# User_Interface.net
KiCad netlist of a schematic drawn in Altium Designer
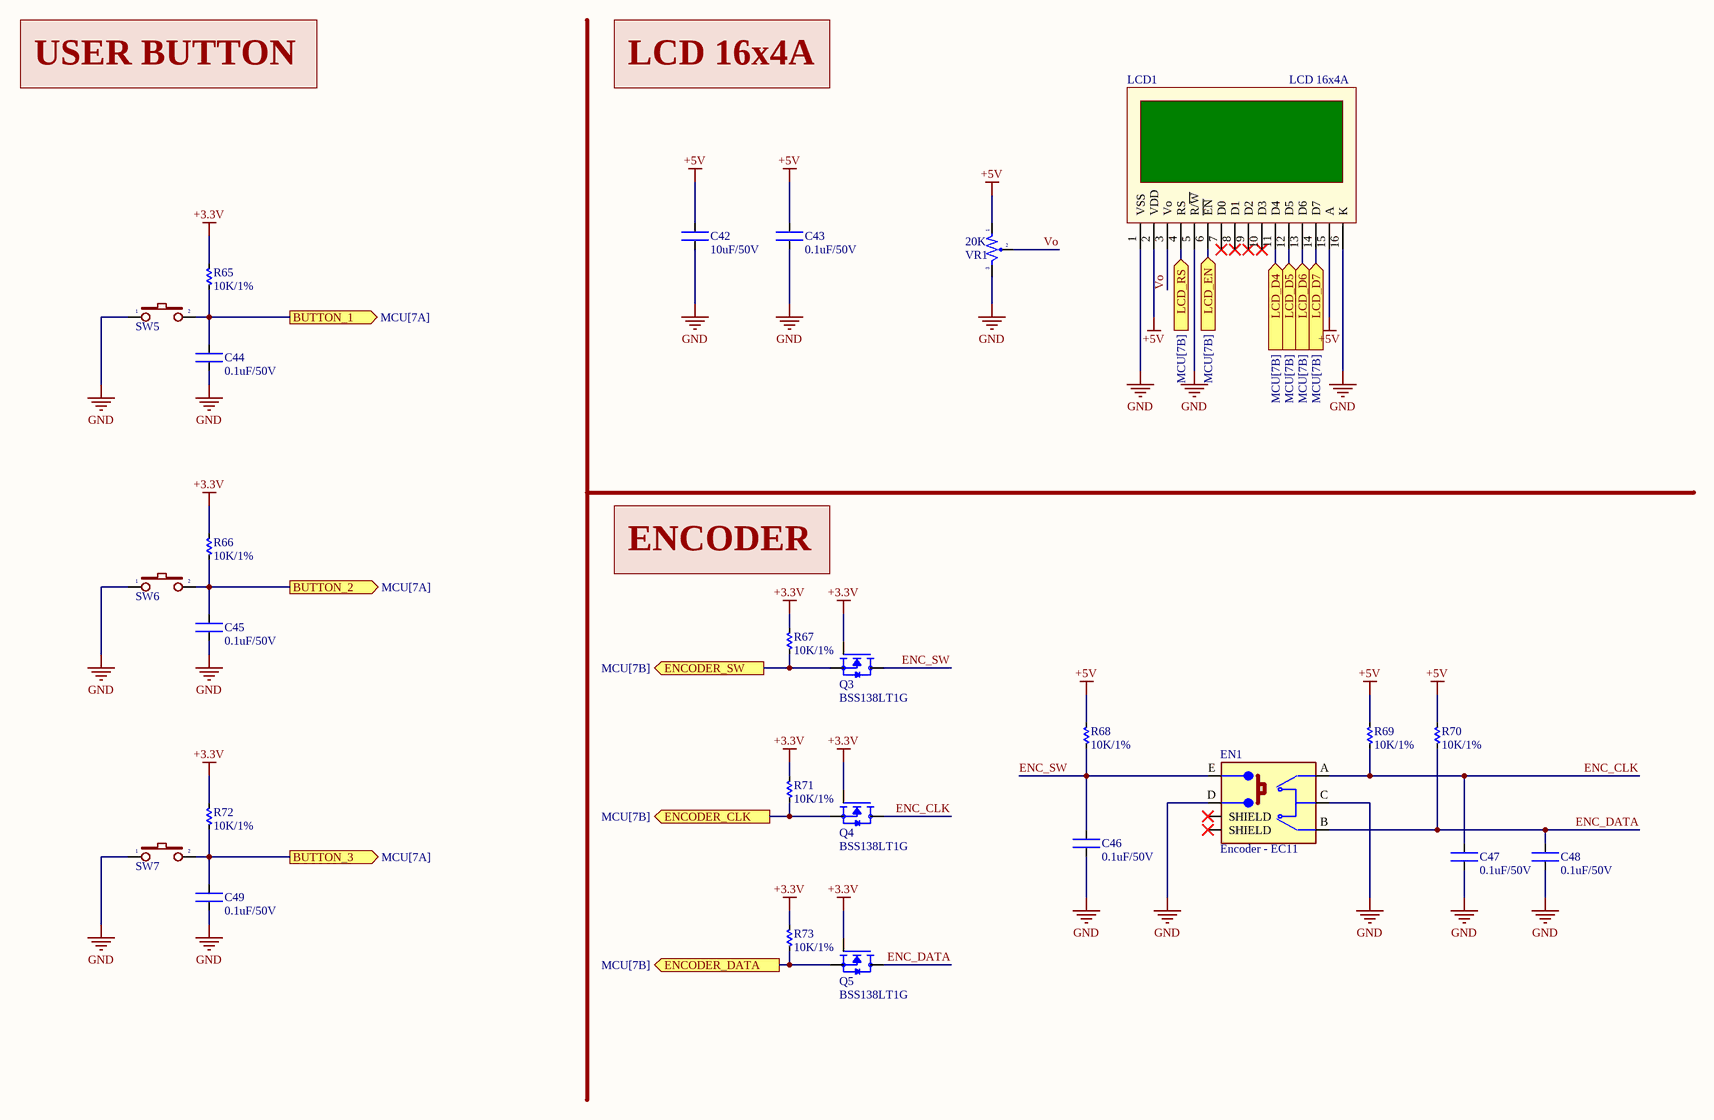
[diagram p0: User_Interface.SchDoc]

(export (version "E")
  (design (tool "Eeschema 10.0.6"))
  (components
    (comp (ref "C42")
      (value "10uF/50V")
      (footprint "CAP - 0603")
      (description "CAPACITOR SMD - KEMET")
      (libsource (lib "NewLibrary") (part "CAPACITOR"))
    )
    (comp (ref "C43")
      (value "0.1uF/50V")
      (footprint "CAP - 0603")
      (description "CAPACITOR SMD - KEMET")
      (libsource (lib "NewLibrary") (part "CAPACITOR"))
    )
    (comp (ref "C44")
      (value "0.1uF/50V")
      (footprint "CAP - 0603")
      (description "CAPACITOR SMD - KEMET")
      (libsource (lib "NewLibrary") (part "CAPACITOR"))
    )
    (comp (ref "C45")
      (value "0.1uF/50V")
      (footprint "CAP - 0603")
      (description "CAPACITOR SMD - KEMET")
      (libsource (lib "NewLibrary") (part "CAPACITOR"))
    )
    (comp (ref "C46")
      (value "0.1uF/50V")
      (footprint "CAP - 0603")
      (description "CAPACITOR SMD - KEMET")
      (libsource (lib "NewLibrary") (part "CAPACITOR"))
    )
    (comp (ref "C47")
      (value "0.1uF/50V")
      (footprint "CAP - 0603")
      (description "CAPACITOR SMD - KEMET")
      (libsource (lib "NewLibrary") (part "CAPACITOR"))
    )
    (comp (ref "C48")
      (value "0.1uF/50V")
      (footprint "CAP - 0603")
      (description "CAPACITOR SMD - KEMET")
      (libsource (lib "NewLibrary") (part "CAPACITOR"))
    )
    (comp (ref "C49")
      (value "0.1uF/50V")
      (footprint "CAP - 0603")
      (description "CAPACITOR SMD - KEMET")
      (libsource (lib "NewLibrary") (part "CAPACITOR"))
    )
    (comp (ref "EN1")
      (value "Encoder - EC11")
      (footprint "Encoder - EC11")
      (description "Bourns PEC11R-4015F-S0024")
      (libsource (lib "NewLibrary") (part "Encoder - EC11"))
    )
    (comp (ref "LCD1")
      (value "LCD 16x4A")
      (footprint "LCD-16x4A-2-Holes")
      (description "Character LCD, 16x4, LED backlight.")
      (libsource (lib "NewLibrary") (part "LCD 16x4A"))
    )
    (comp (ref "Q3")
      (value "BSS138LT1G")
      (footprint "SOT23-3 - BSS138LT1G")
      (description "N-Channel 50 V 200mA (Ta) 225mW (Ta) Surface Mount SOT-23-3 (TO-236)")
      (libsource (lib "NewLibrary") (part "BSS138LT1G"))
    )
    (comp (ref "Q4")
      (value "BSS138LT1G")
      (footprint "SOT23-3 - BSS138LT1G")
      (description "N-Channel 50 V 200mA (Ta) 225mW (Ta) Surface Mount SOT-23-3 (TO-236)")
      (libsource (lib "NewLibrary") (part "BSS138LT1G"))
    )
    (comp (ref "Q5")
      (value "BSS138LT1G")
      (footprint "SOT23-3 - BSS138LT1G")
      (description "N-Channel 50 V 200mA (Ta) 225mW (Ta) Surface Mount SOT-23-3 (TO-236)")
      (libsource (lib "NewLibrary") (part "BSS138LT1G"))
    )
    (comp (ref "R65")
      (value "10K/1%")
      (footprint "RES - 0603")
      (description "Resistor SMD - YAGEO")
      (libsource (lib "NewLibrary") (part "RESISTOR"))
    )
    (comp (ref "R66")
      (value "10K/1%")
      (footprint "RES - 0603")
      (description "Resistor SMD - YAGEO")
      (libsource (lib "NewLibrary") (part "RESISTOR"))
    )
    (comp (ref "R67")
      (value "10K/1%")
      (footprint "RES - 0603")
      (description "Resistor SMD - YAGEO")
      (libsource (lib "NewLibrary") (part "RESISTOR"))
    )
    (comp (ref "R68")
      (value "10K/1%")
      (footprint "RES - 0603")
      (description "Resistor SMD - YAGEO")
      (libsource (lib "NewLibrary") (part "RESISTOR"))
    )
    (comp (ref "R69")
      (value "10K/1%")
      (footprint "RES - 0603")
      (description "Resistor SMD - YAGEO")
      (libsource (lib "NewLibrary") (part "RESISTOR"))
    )
    (comp (ref "R70")
      (value "10K/1%")
      (footprint "RES - 0603")
      (description "Resistor SMD - YAGEO")
      (libsource (lib "NewLibrary") (part "RESISTOR"))
    )
    (comp (ref "R71")
      (value "10K/1%")
      (footprint "RES - 0603")
      (description "Resistor SMD - YAGEO")
      (libsource (lib "NewLibrary") (part "RESISTOR"))
    )
    (comp (ref "R72")
      (value "10K/1%")
      (footprint "RES - 0603")
      (description "Resistor SMD - YAGEO")
      (libsource (lib "NewLibrary") (part "RESISTOR"))
    )
    (comp (ref "R73")
      (value "10K/1%")
      (footprint "RES - 0603")
      (description "Resistor SMD - YAGEO")
      (libsource (lib "NewLibrary") (part "RESISTOR"))
    )
    (comp (ref "SW5")
      (value "Button 4 Pins")
      (footprint "SW-SMD-6x6mm")
      (description "DIP Button 4 Pins")
      (libsource (lib "NewLibrary") (part "Button 4 Pins"))
    )
    (comp (ref "SW6")
      (value "Button 4 Pins")
      (footprint "SW-SMD-6x6mm")
      (description "DIP Button 4 Pins")
      (libsource (lib "NewLibrary") (part "Button 4 Pins"))
    )
    (comp (ref "SW7")
      (value "Button 4 Pins")
      (footprint "SW-SMD-6x6mm")
      (description "DIP Button 4 Pins")
      (libsource (lib "NewLibrary") (part "Button 4 Pins"))
    )
    (comp (ref "VR1")
      (value "20K")
      (footprint "VR 3x3")
      (description "VR")
      (libsource (lib "NewLibrary") (part "VARIABLE RESISTOR"))
    )
  )
  (nets
    (net (code "1") (name "+3.3V") (class "Default")
      (node (ref "Q3") (pin "1") (pinfunction "G_1") (pintype "passive"))
      (node (ref "Q4") (pin "1") (pinfunction "G_1") (pintype "passive"))
      (node (ref "Q5") (pin "1") (pinfunction "G_1") (pintype "passive"))
      (node (ref "R65") (pin "2") (pinfunction "2_2") (pintype "passive"))
      (node (ref "R66") (pin "2") (pinfunction "2_2") (pintype "passive"))
      (node (ref "R67") (pin "2") (pinfunction "2_2") (pintype "passive"))
      (node (ref "R71") (pin "2") (pinfunction "2_2") (pintype "passive"))
      (node (ref "R72") (pin "1") (pinfunction "1_1") (pintype "passive"))
      (node (ref "R73") (pin "2") (pinfunction "2_2") (pintype "passive"))
    )
    (net (code "2") (name "+5V") (class "Default")
      (node (ref "C42") (pin "2") (pinfunction "2_2") (pintype "passive"))
      (node (ref "C43") (pin "2") (pinfunction "2_2") (pintype "passive"))
      (node (ref "LCD1") (pin "15") (pinfunction "A_15") (pintype "passive"))
      (node (ref "LCD1") (pin "2") (pinfunction "VDD_2") (pintype "passive"))
      (node (ref "R68") (pin "2") (pinfunction "2_2") (pintype "passive"))
      (node (ref "R69") (pin "2") (pinfunction "2_2") (pintype "passive"))
      (node (ref "R70") (pin "2") (pinfunction "2_2") (pintype "passive"))
      (node (ref "VR1") (pin "1") (pinfunction "1_1") (pintype "passive"))
    )
    (net (code "3") (name "/BUTTON_1") (class "Default")
      (node (ref "C44") (pin "2") (pinfunction "2_2") (pintype "passive"))
      (node (ref "R65") (pin "1") (pinfunction "1_1") (pintype "passive"))
      (node (ref "SW5") (pin "2") (pinfunction "2_2") (pintype "passive"))
    )
    (net (code "4") (name "/BUTTON_2") (class "Default")
      (node (ref "C45") (pin "2") (pinfunction "2_2") (pintype "passive"))
      (node (ref "R66") (pin "1") (pinfunction "1_1") (pintype "passive"))
      (node (ref "SW6") (pin "2") (pinfunction "2_2") (pintype "passive"))
    )
    (net (code "5") (name "/BUTTON_3") (class "Default")
      (node (ref "C49") (pin "2") (pinfunction "2_2") (pintype "passive"))
      (node (ref "R72") (pin "2") (pinfunction "2_2") (pintype "passive"))
      (node (ref "SW7") (pin "2") (pinfunction "2_2") (pintype "passive"))
    )
    (net (code "6") (name "/ENCODER_CLK") (class "Default")
      (node (ref "Q4") (pin "2") (pinfunction "S_2") (pintype "passive"))
      (node (ref "R71") (pin "1") (pinfunction "1_1") (pintype "passive"))
    )
    (net (code "7") (name "/ENCODER_DATA") (class "Default")
      (node (ref "Q5") (pin "2") (pinfunction "S_2") (pintype "passive"))
      (node (ref "R73") (pin "1") (pinfunction "1_1") (pintype "passive"))
    )
    (net (code "8") (name "/ENCODER_SW") (class "Default")
      (node (ref "Q3") (pin "2") (pinfunction "S_2") (pintype "passive"))
      (node (ref "R67") (pin "1") (pinfunction "1_1") (pintype "passive"))
    )
    (net (code "9") (name "/ENC_CLK") (class "Default")
      (node (ref "C47") (pin "2") (pinfunction "2_2") (pintype "passive"))
      (node (ref "EN1") (pin "A") (pinfunction "A_A") (pintype "passive"))
      (node (ref "Q4") (pin "3") (pinfunction "D_3") (pintype "passive"))
      (node (ref "R69") (pin "1") (pinfunction "1_1") (pintype "passive"))
    )
    (net (code "10") (name "/ENC_DATA") (class "Default")
      (node (ref "C48") (pin "2") (pinfunction "2_2") (pintype "passive"))
      (node (ref "EN1") (pin "B") (pinfunction "B_B") (pintype "passive"))
      (node (ref "Q5") (pin "3") (pinfunction "D_3") (pintype "passive"))
      (node (ref "R70") (pin "1") (pinfunction "1_1") (pintype "passive"))
    )
    (net (code "11") (name "/ENC_SW") (class "Default")
      (node (ref "C46") (pin "2") (pinfunction "2_2") (pintype "passive"))
      (node (ref "EN1") (pin "E") (pinfunction "S2_E") (pintype "passive"))
      (node (ref "Q3") (pin "3") (pinfunction "D_3") (pintype "passive"))
      (node (ref "R68") (pin "1") (pinfunction "1_1") (pintype "passive"))
    )
    (net (code "12") (name "/LCD_D4") (class "Default")
      (node (ref "LCD1") (pin "11") (pinfunction "D4_11") (pintype "passive"))
    )
    (net (code "13") (name "/LCD_D5") (class "Default")
      (node (ref "LCD1") (pin "12") (pinfunction "D5_12") (pintype "passive"))
    )
    (net (code "14") (name "/LCD_D6") (class "Default")
      (node (ref "LCD1") (pin "13") (pinfunction "D6_13") (pintype "passive"))
    )
    (net (code "15") (name "/LCD_D7") (class "Default")
      (node (ref "LCD1") (pin "14") (pinfunction "D7_14") (pintype "passive"))
    )
    (net (code "16") (name "/LCD_EN") (class "Default")
      (node (ref "LCD1") (pin "6") (pinfunction "~{EN}_6") (pintype "passive"))
    )
    (net (code "17") (name "/LCD_RS") (class "Default")
      (node (ref "LCD1") (pin "4") (pinfunction "RS_4") (pintype "passive"))
    )
    (net (code "18") (name "/Vo") (class "Default")
      (node (ref "LCD1") (pin "3") (pinfunction "Vo_3") (pintype "passive"))
      (node (ref "VR1") (pin "2") (pinfunction "2_2") (pintype "passive"))
    )
    (net (code "19") (name "GND") (class "Default")
      (node (ref "C42") (pin "1") (pinfunction "1_1") (pintype "passive"))
      (node (ref "C43") (pin "1") (pinfunction "1_1") (pintype "passive"))
      (node (ref "C44") (pin "1") (pinfunction "1_1") (pintype "passive"))
      (node (ref "C45") (pin "1") (pinfunction "1_1") (pintype "passive"))
      (node (ref "C46") (pin "1") (pinfunction "1_1") (pintype "passive"))
      (node (ref "C47") (pin "1") (pinfunction "1_1") (pintype "passive"))
      (node (ref "C48") (pin "1") (pinfunction "1_1") (pintype "passive"))
      (node (ref "C49") (pin "1") (pinfunction "1_1") (pintype "passive"))
      (node (ref "EN1") (pin "C") (pinfunction "C_C") (pintype "passive"))
      (node (ref "EN1") (pin "D") (pinfunction "S1_D") (pintype "passive"))
      (node (ref "LCD1") (pin "1") (pinfunction "VSS_1") (pintype "passive"))
      (node (ref "LCD1") (pin "16") (pinfunction "K_16") (pintype "passive"))
      (node (ref "LCD1") (pin "5") (pinfunction "R/~{W}_5") (pintype "passive"))
      (node (ref "SW5") (pin "1") (pinfunction "1_1") (pintype "passive"))
      (node (ref "SW6") (pin "1") (pinfunction "1_1") (pintype "passive"))
      (node (ref "SW7") (pin "1") (pinfunction "1_1") (pintype "passive"))
      (node (ref "VR1") (pin "3") (pinfunction "3_3") (pintype "passive"))
    )
    (net (code "20") (name "unconnected-(EN1-SHIELD-PadSH1)") (class "Default")
      (node (ref "EN1") (pin "SH1") (pinfunction "SHIELD_SH1") (pintype "passive+no_connect"))
    )
    (net (code "21") (name "unconnected-(EN1-SHIELD-PadSH2)") (class "Default")
      (node (ref "EN1") (pin "SH2") (pinfunction "SHIELD_SH2") (pintype "passive+no_connect"))
    )
    (net (code "22") (name "unconnected-(LCD1-D0-Pad7)") (class "Default")
      (node (ref "LCD1") (pin "7") (pinfunction "D0_7") (pintype "passive+no_connect"))
    )
    (net (code "23") (name "unconnected-(LCD1-D1-Pad8)") (class "Default")
      (node (ref "LCD1") (pin "8") (pinfunction "D1_8") (pintype "passive+no_connect"))
    )
    (net (code "24") (name "unconnected-(LCD1-D2-Pad9)") (class "Default")
      (node (ref "LCD1") (pin "9") (pinfunction "D2_9") (pintype "passive+no_connect"))
    )
    (net (code "25") (name "unconnected-(LCD1-D3-Pad10)") (class "Default")
      (node (ref "LCD1") (pin "10") (pinfunction "D3_10") (pintype "passive+no_connect"))
    )
  )
)
